# 1-Schematic_Smart_Flood_Detection_System.net
KiCad netlist of a schematic drawn in EasyEDA
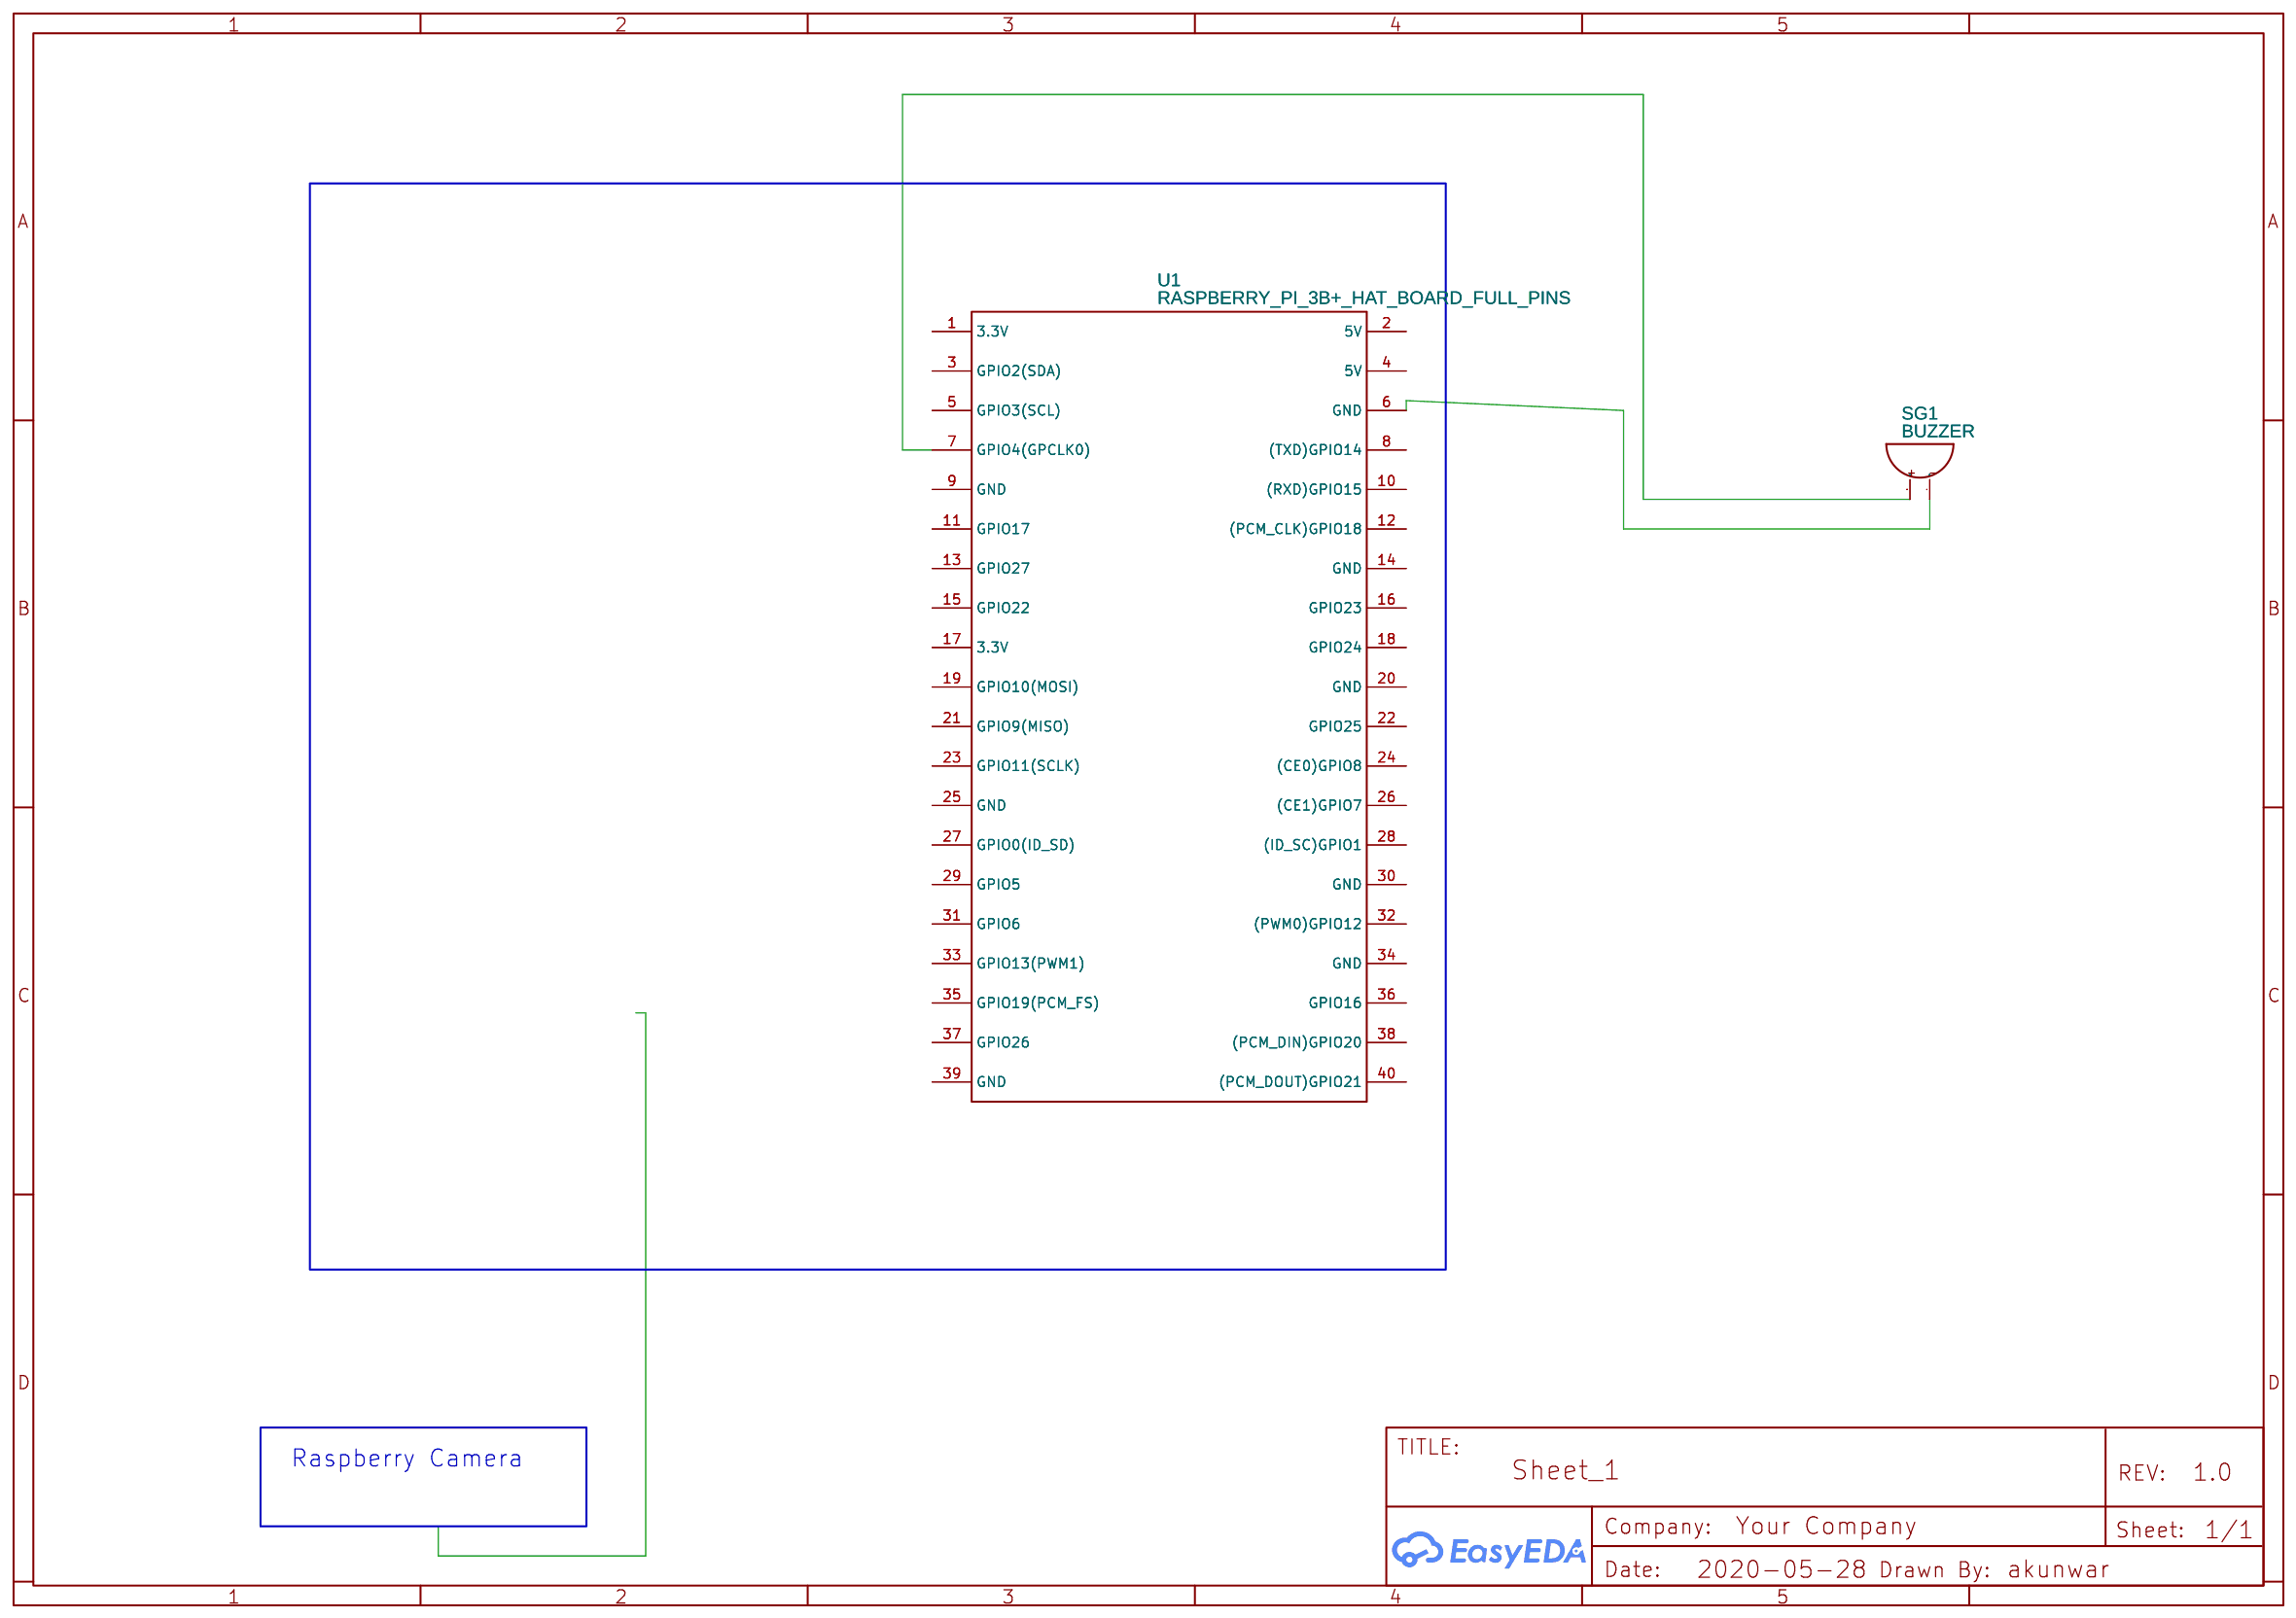
[diagram p0: schematic sheet]

(export (version "E")
  (design (tool "Eeschema 10.0.6"))
  (components
    (comp (ref "SG1") (value "BUZZER") (libsource (lib "") (part "BUZZER")))
    (comp (ref "U1")
      (value "RASPBERRY_PI_3B+_HAT_BOARD_FULL_PINS")
      (fields (field (name "BOM_Manufacturer Part") "Raspberry-Pi-3B-Plus-HAT-Board"))
      (libsource (lib "") (part "RASPBERRY_PI_3B_PLUS_HAT_BOARD_FULL_PINS"))
    )
  )
  (nets
    (net (code "1") (name "Net-(SG1-1)") (class "Default")
      (node (ref "SG1") (pin "+") (pinfunction "1_+") (pintype "unspecified"))
      (node (ref "U1") (pin "7") (pinfunction "GPIO4(GPCLK0)_7") (pintype "unspecified"))
    )
    (net (code "2") (name "Net-(SG1-2)") (class "Default")
      (node (ref "SG1") (pin "-") (pinfunction "2_-") (pintype "unspecified"))
      (node (ref "U1") (pin "6") (pinfunction "GND_6") (pintype "unspecified"))
    )
    (net (code "3") (name "unconnected-(U1-(CE0)GPIO8-Pad24)") (class "Default")
      (node (ref "U1") (pin "24") (pinfunction "(CE0)GPIO8_24") (pintype "unspecified"))
    )
    (net (code "4") (name "unconnected-(U1-(CE1)GPIO7-Pad26)") (class "Default")
      (node (ref "U1") (pin "26") (pinfunction "(CE1)GPIO7_26") (pintype "unspecified"))
    )
    (net (code "5") (name "unconnected-(U1-(ID_SC)GPIO1-Pad28)") (class "Default")
      (node (ref "U1") (pin "28") (pinfunction "(ID_SC)GPIO1_28") (pintype "unspecified"))
    )
    (net (code "6") (name "unconnected-(U1-(PCM_CLK)GPIO18-Pad12)") (class "Default")
      (node (ref "U1") (pin "12") (pinfunction "(PCM_CLK)GPIO18_12") (pintype "unspecified"))
    )
    (net (code "7") (name "unconnected-(U1-(PCM_DIN)GPIO20-Pad38)") (class "Default")
      (node (ref "U1") (pin "38") (pinfunction "(PCM_DIN)GPIO20_38") (pintype "unspecified"))
    )
    (net (code "8") (name "unconnected-(U1-(PCM_DOUT)GPIO21-Pad40)") (class "Default")
      (node (ref "U1") (pin "40") (pinfunction "(PCM_DOUT)GPIO21_40") (pintype "unspecified"))
    )
    (net (code "9") (name "unconnected-(U1-(PWM0)GPIO12-Pad32)") (class "Default")
      (node (ref "U1") (pin "32") (pinfunction "(PWM0)GPIO12_32") (pintype "unspecified"))
    )
    (net (code "10") (name "unconnected-(U1-(RXD)GPIO15-Pad10)") (class "Default")
      (node (ref "U1") (pin "10") (pinfunction "(RXD)GPIO15_10") (pintype "unspecified"))
    )
    (net (code "11") (name "unconnected-(U1-(TXD)GPIO14-Pad8)") (class "Default")
      (node (ref "U1") (pin "8") (pinfunction "(TXD)GPIO14_8") (pintype "unspecified"))
    )
    (net (code "12") (name "unconnected-(U1-3.3V-Pad1)") (class "Default")
      (node (ref "U1") (pin "1") (pinfunction "3.3V_1") (pintype "unspecified"))
    )
    (net (code "13") (name "unconnected-(U1-3.3V-Pad17)") (class "Default")
      (node (ref "U1") (pin "17") (pinfunction "3.3V_17") (pintype "unspecified"))
    )
    (net (code "14") (name "unconnected-(U1-5V-Pad2)") (class "Default")
      (node (ref "U1") (pin "2") (pinfunction "5V_2") (pintype "unspecified"))
    )
    (net (code "15") (name "unconnected-(U1-5V-Pad4)") (class "Default")
      (node (ref "U1") (pin "4") (pinfunction "5V_4") (pintype "unspecified"))
    )
    (net (code "16") (name "unconnected-(U1-GND-Pad9)") (class "Default")
      (node (ref "U1") (pin "9") (pinfunction "GND_9") (pintype "unspecified"))
    )
    (net (code "17") (name "unconnected-(U1-GND-Pad14)") (class "Default")
      (node (ref "U1") (pin "14") (pinfunction "GND_14") (pintype "unspecified"))
    )
    (net (code "18") (name "unconnected-(U1-GND-Pad20)") (class "Default")
      (node (ref "U1") (pin "20") (pinfunction "GND_20") (pintype "unspecified"))
    )
    (net (code "19") (name "unconnected-(U1-GND-Pad25)") (class "Default")
      (node (ref "U1") (pin "25") (pinfunction "GND_25") (pintype "unspecified"))
    )
    (net (code "20") (name "unconnected-(U1-GND-Pad30)") (class "Default")
      (node (ref "U1") (pin "30") (pinfunction "GND_30") (pintype "unspecified"))
    )
    (net (code "21") (name "unconnected-(U1-GND-Pad34)") (class "Default")
      (node (ref "U1") (pin "34") (pinfunction "GND_34") (pintype "unspecified"))
    )
    (net (code "22") (name "unconnected-(U1-GND-Pad39)") (class "Default")
      (node (ref "U1") (pin "39") (pinfunction "GND_39") (pintype "unspecified"))
    )
    (net (code "23") (name "unconnected-(U1-GPIO0(ID_SD)-Pad27)") (class "Default")
      (node (ref "U1") (pin "27") (pinfunction "GPIO0(ID_SD)_27") (pintype "unspecified"))
    )
    (net (code "24") (name "unconnected-(U1-GPIO2(SDA)-Pad3)") (class "Default")
      (node (ref "U1") (pin "3") (pinfunction "GPIO2(SDA)_3") (pintype "unspecified"))
    )
    (net (code "25") (name "unconnected-(U1-GPIO3(SCL)-Pad5)") (class "Default")
      (node (ref "U1") (pin "5") (pinfunction "GPIO3(SCL)_5") (pintype "unspecified"))
    )
    (net (code "26") (name "unconnected-(U1-GPIO5-Pad29)") (class "Default")
      (node (ref "U1") (pin "29") (pinfunction "GPIO5_29") (pintype "unspecified"))
    )
    (net (code "27") (name "unconnected-(U1-GPIO6-Pad31)") (class "Default")
      (node (ref "U1") (pin "31") (pinfunction "GPIO6_31") (pintype "unspecified"))
    )
    (net (code "28") (name "unconnected-(U1-GPIO9(MISO)-Pad21)") (class "Default")
      (node (ref "U1") (pin "21") (pinfunction "GPIO9(MISO)_21") (pintype "unspecified"))
    )
    (net (code "29") (name "unconnected-(U1-GPIO10(MOSI)-Pad19)") (class "Default")
      (node (ref "U1") (pin "19") (pinfunction "GPIO10(MOSI)_19") (pintype "unspecified"))
    )
    (net (code "30") (name "unconnected-(U1-GPIO11(SCLK)-Pad23)") (class "Default")
      (node (ref "U1") (pin "23") (pinfunction "GPIO11(SCLK)_23") (pintype "unspecified"))
    )
    (net (code "31") (name "unconnected-(U1-GPIO13(PWM1)-Pad33)") (class "Default")
      (node (ref "U1") (pin "33") (pinfunction "GPIO13(PWM1)_33") (pintype "unspecified"))
    )
    (net (code "32") (name "unconnected-(U1-GPIO16-Pad36)") (class "Default")
      (node (ref "U1") (pin "36") (pinfunction "GPIO16_36") (pintype "unspecified"))
    )
    (net (code "33") (name "unconnected-(U1-GPIO17-Pad11)") (class "Default")
      (node (ref "U1") (pin "11") (pinfunction "GPIO17_11") (pintype "unspecified"))
    )
    (net (code "34") (name "unconnected-(U1-GPIO19(PCM_FS)-Pad35)") (class "Default")
      (node (ref "U1") (pin "35") (pinfunction "GPIO19(PCM_FS)_35") (pintype "unspecified"))
    )
    (net (code "35") (name "unconnected-(U1-GPIO22-Pad15)") (class "Default")
      (node (ref "U1") (pin "15") (pinfunction "GPIO22_15") (pintype "unspecified"))
    )
    (net (code "36") (name "unconnected-(U1-GPIO23-Pad16)") (class "Default")
      (node (ref "U1") (pin "16") (pinfunction "GPIO23_16") (pintype "unspecified"))
    )
    (net (code "37") (name "unconnected-(U1-GPIO24-Pad18)") (class "Default")
      (node (ref "U1") (pin "18") (pinfunction "GPIO24_18") (pintype "unspecified"))
    )
    (net (code "38") (name "unconnected-(U1-GPIO25-Pad22)") (class "Default")
      (node (ref "U1") (pin "22") (pinfunction "GPIO25_22") (pintype "unspecified"))
    )
    (net (code "39") (name "unconnected-(U1-GPIO26-Pad37)") (class "Default")
      (node (ref "U1") (pin "37") (pinfunction "GPIO26_37") (pintype "unspecified"))
    )
    (net (code "40") (name "unconnected-(U1-GPIO27-Pad13)") (class "Default")
      (node (ref "U1") (pin "13") (pinfunction "GPIO27_13") (pintype "unspecified"))
    )
  )
)
